# New_Project_2024-11-29_16-29-11.net
KiCad netlist of a schematic drawn in EasyEDA Pro
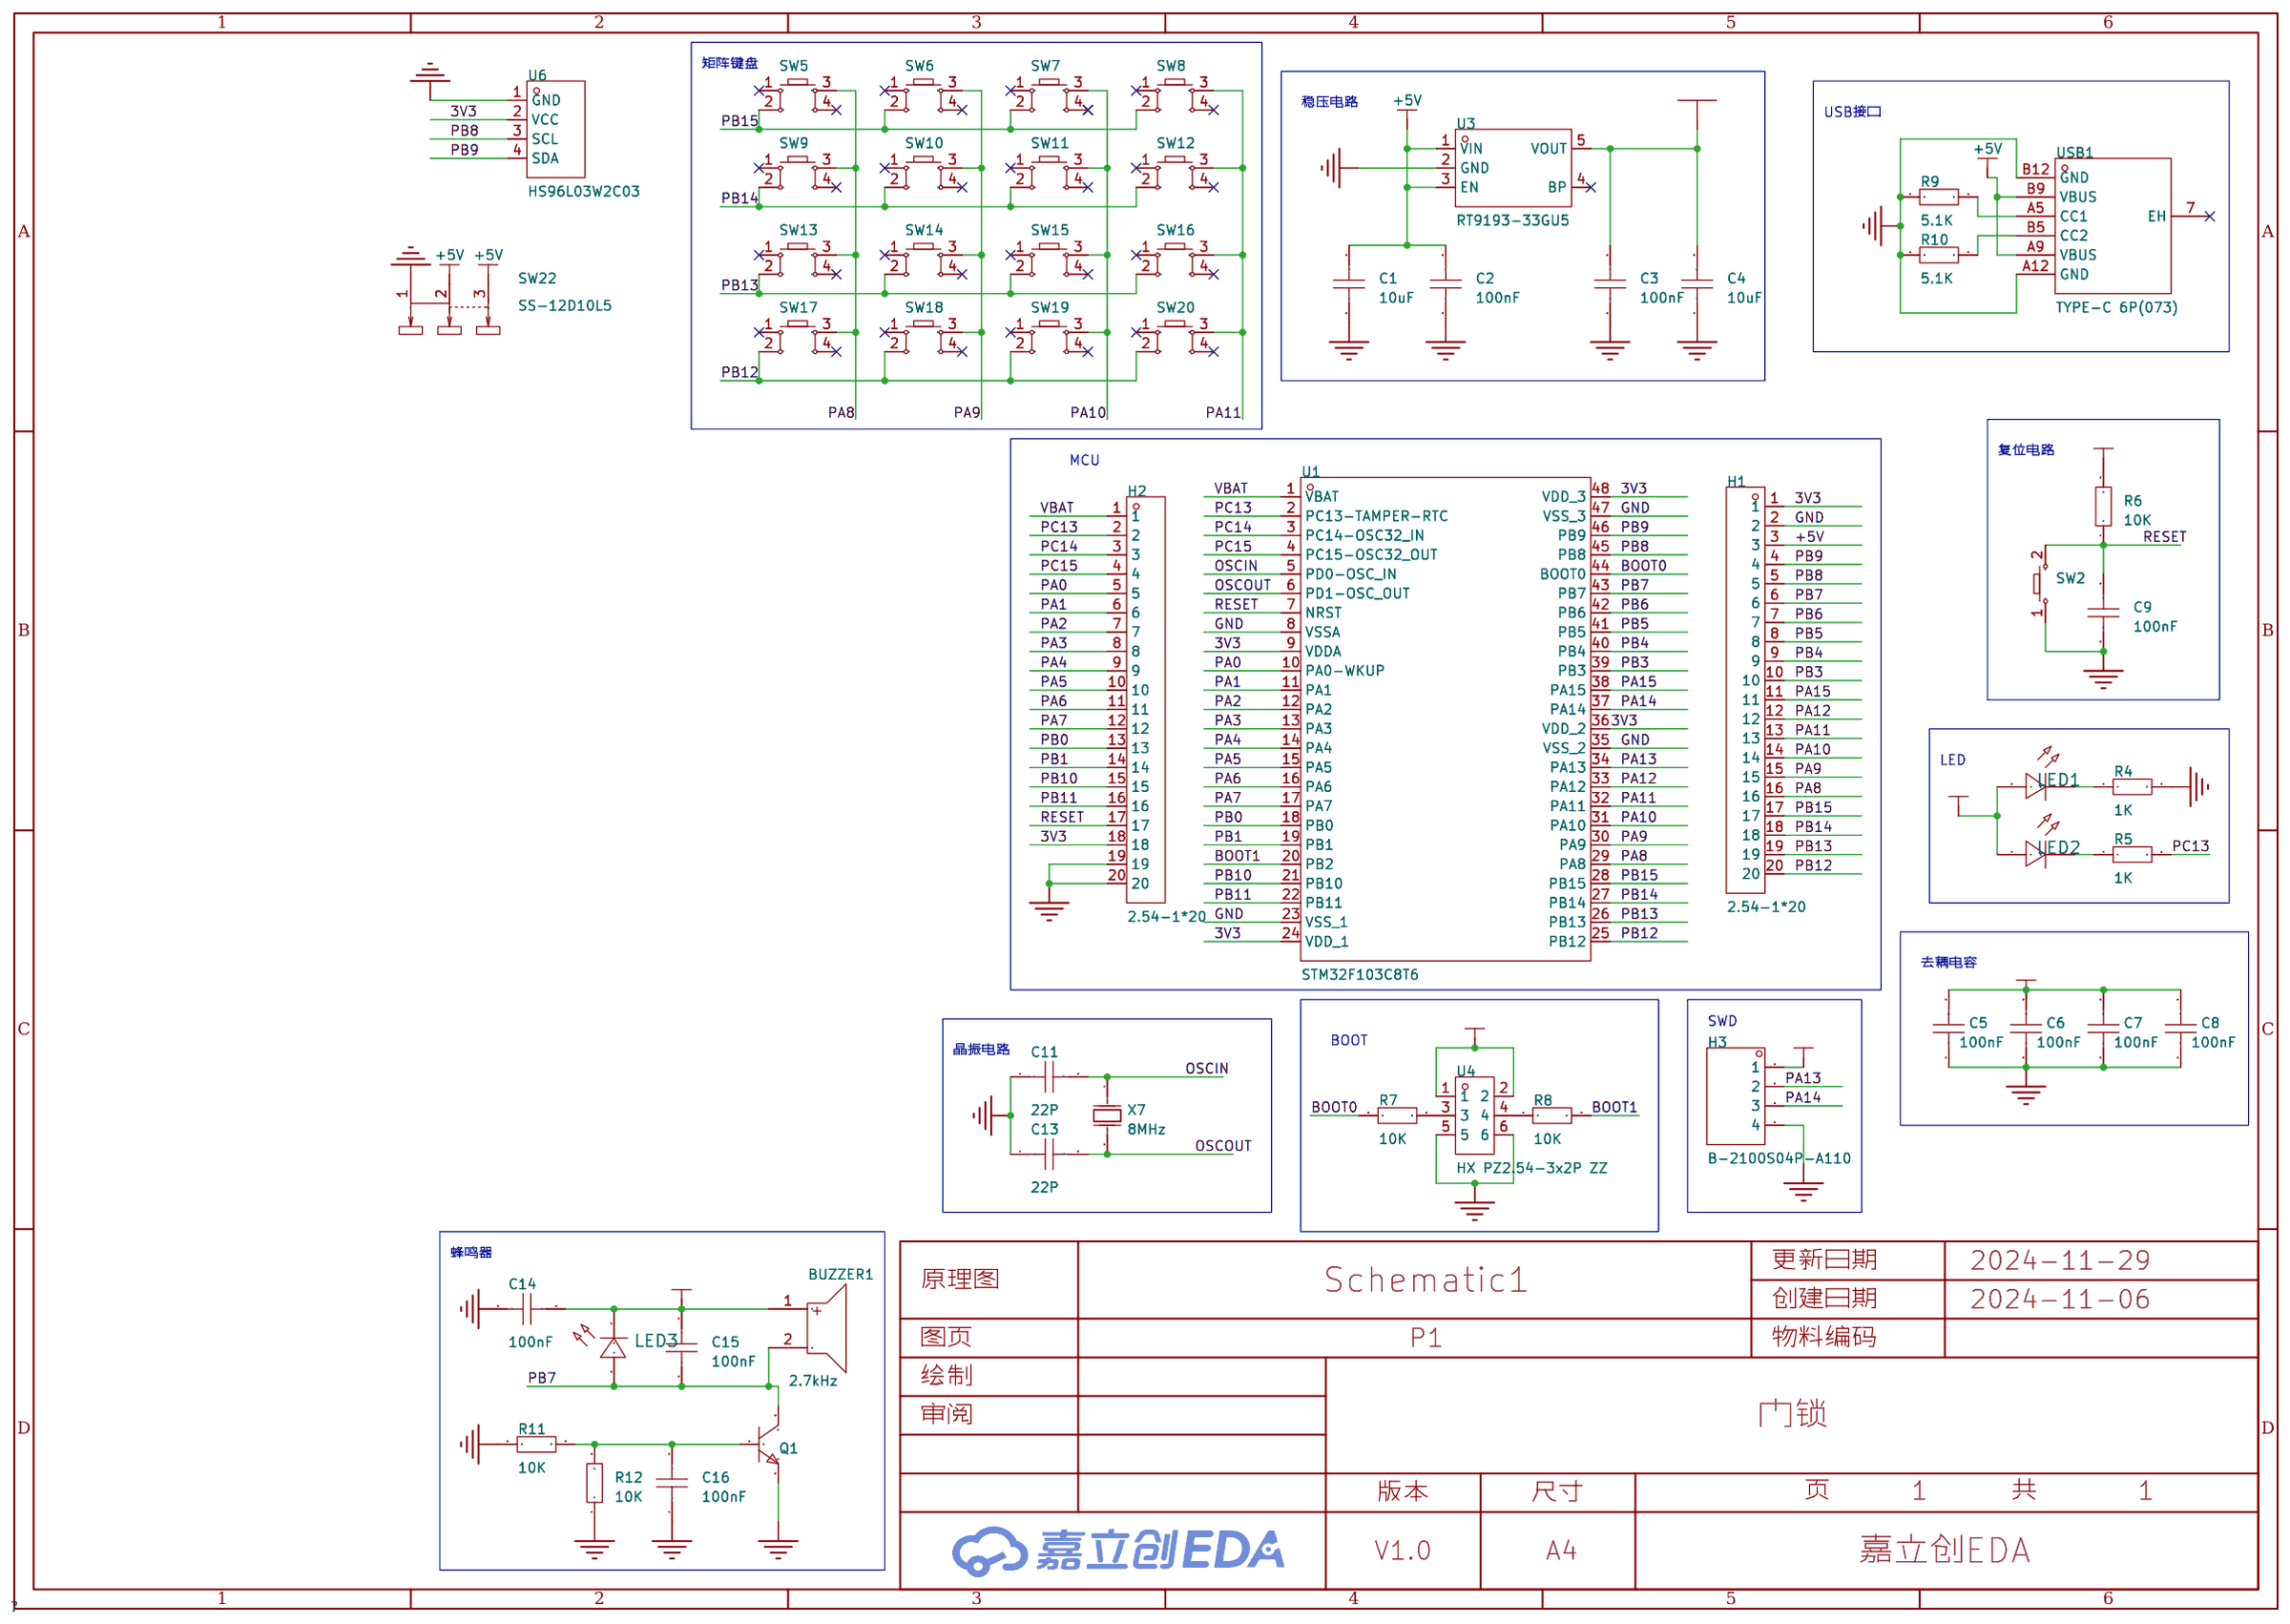
[diagram p0: schematic sheet]

(export (version "E")
  (design (tool "Eeschema 10.0.6"))
  (components
    (comp (ref "BUZZER1")
      (value "2.7kHz")
      (footprint "easyedapro:BUZ-TH_BD9.0-P4.00-D0.6-FD")
      (description "驱动方式:无源(外部驱动);构造类型:电磁式;频率:2.7kHz;声压(SPL):85dB@3V,10cm;")
      (fields (field (name "Manufacturer Part") "QMB-09B-03") (field (name "Manufacturer") "华能"))
      (libsource (lib "easyedapro") (part "QMB-09B-03"))
    )
    (comp (ref "C1")
      (value "10uF")
      (footprint "easyedapro:C0805")
      (libsource (lib "easyedapro") (part "CapAcitance"))
    )
    (comp (ref "C2")
      (value "100nF")
      (footprint "easyedapro:C0805")
      (libsource (lib "easyedapro") (part "CapAcitance"))
    )
    (comp (ref "C3")
      (value "100nF")
      (footprint "easyedapro:C0805")
      (libsource (lib "easyedapro") (part "CapAcitance"))
    )
    (comp (ref "C4")
      (value "10uF")
      (footprint "easyedapro:C0805")
      (libsource (lib "easyedapro") (part "CapAcitance"))
    )
    (comp (ref "C5")
      (value "100nF")
      (footprint "easyedapro:C0805")
      (libsource (lib "easyedapro") (part "CapAcitance"))
    )
    (comp (ref "C6")
      (value "100nF")
      (footprint "easyedapro:C0805")
      (libsource (lib "easyedapro") (part "CapAcitance"))
    )
    (comp (ref "C7")
      (value "100nF")
      (footprint "easyedapro:C0805")
      (libsource (lib "easyedapro") (part "CapAcitance"))
    )
    (comp (ref "C8")
      (value "100nF")
      (footprint "easyedapro:C0805")
      (libsource (lib "easyedapro") (part "CapAcitance"))
    )
    (comp (ref "C9")
      (value "100nF")
      (footprint "easyedapro:C0805")
      (libsource (lib "easyedapro") (part "CapAcitance"))
    )
    (comp (ref "C11")
      (value "22P")
      (footprint "easyedapro:C0805")
      (libsource (lib "easyedapro") (part "CapAcitance"))
    )
    (comp (ref "C13")
      (value "22P")
      (footprint "easyedapro:C0805")
      (libsource (lib "easyedapro") (part "CapAcitance"))
    )
    (comp (ref "C14")
      (value "100nF")
      (footprint "easyedapro:C0805")
      (libsource (lib "easyedapro") (part "CapAcitance"))
    )
    (comp (ref "C15")
      (value "100nF")
      (footprint "easyedapro:C0805")
      (libsource (lib "easyedapro") (part "CapAcitance"))
    )
    (comp (ref "C16")
      (value "100nF")
      (footprint "easyedapro:C0805")
      (libsource (lib "easyedapro") (part "CapAcitance"))
    )
    (comp (ref "H1")
      (value "2.54-1*20")
      (footprint "easyedapro:HDR-TH_20P-P2.54-V-M")
      (description "插针结构:1x20P;间距:2.54mm;排数:单排;总PIN位数:20P;")
      (fields (field (name "Manufacturer") "ZHOURI(洲日)"))
      (libsource (lib "easyedapro") (part "2.54-1*20"))
    )
    (comp (ref "H2")
      (value "2.54-1*20")
      (footprint "easyedapro:HDR-TH_20P-P2.54-V-M")
      (description "插针结构:1x20P;间距:2.54mm;排数:单排;总PIN位数:20P;")
      (fields (field (name "Manufacturer") "ZHOURI(洲日)"))
      (libsource (lib "easyedapro") (part "2.54-1*20"))
    )
    (comp (ref "H3")
      (value "B-2100S04P-A110")
      (footprint "easyedapro:HDR-TH_4P-P2.54-V-M")
      (fields (field (name "Manufacturer") "Ckmtw(灿科盟)"))
      (libsource (lib "easyedapro") (part "Header-Male-2.54_1x4"))
    )
    (comp (ref "LED1")
      (value "~")
      (footprint "easyedapro:LED_0603")
      (libsource (lib "easyedapro") (part "LED_R"))
    )
    (comp (ref "LED2")
      (value "~")
      (footprint "easyedapro:LED_0603")
      (libsource (lib "easyedapro") (part "LED_R"))
    )
    (comp (ref "LED3")
      (value "~")
      (footprint "easyedapro:LED_0603")
      (libsource (lib "easyedapro") (part "LED_R"))
    )
    (comp (ref "Q1")
      (value "~")
      (footprint "easyedapro:S8050_SOT-23")
      (libsource (lib "easyedapro") (part "NPN"))
    )
    (comp (ref "R4") (value "1K") (footprint "easyedapro:R0603") (libsource (lib "easyedapro") (part "电阻")))
    (comp (ref "R5") (value "1K") (footprint "easyedapro:R0603") (libsource (lib "easyedapro") (part "电阻")))
    (comp (ref "R6") (value "10K") (footprint "easyedapro:R0603") (libsource (lib "easyedapro") (part "电阻")))
    (comp (ref "R7") (value "10K") (footprint "easyedapro:R0603") (libsource (lib "easyedapro") (part "电阻")))
    (comp (ref "R8") (value "10K") (footprint "easyedapro:R0603") (libsource (lib "easyedapro") (part "电阻")))
    (comp (ref "R9") (value "5.1K") (footprint "easyedapro:R0603") (libsource (lib "easyedapro") (part "电阻")))
    (comp (ref "R10")
      (value "5.1K")
      (footprint "easyedapro:R0603")
      (libsource (lib "easyedapro") (part "电阻"))
    )
    (comp (ref "R11") (value "10K") (footprint "easyedapro:R0603") (libsource (lib "easyedapro") (part "电阻")))
    (comp (ref "R12") (value "10K") (footprint "easyedapro:R0603") (libsource (lib "easyedapro") (part "电阻")))
    (comp (ref "SW2")
      (value "~")
      (footprint "easyedapro:Key_SMD_3.6x6.1x2.5")
      (libsource (lib "easyedapro") (part "轻触按键x2"))
    )
    (comp (ref "SW5")
      (value "~")
      (footprint "easyedapro:SW-SMD_4P-L6.0-W6.0-P4.50-LS9.0-2")
      (libsource (lib "easyedapro") (part "轻触按键"))
    )
    (comp (ref "SW6")
      (value "~")
      (footprint "easyedapro:SW-SMD_4P-L6.0-W6.0-P4.50-LS9.0-2")
      (libsource (lib "easyedapro") (part "轻触按键"))
    )
    (comp (ref "SW7")
      (value "~")
      (footprint "easyedapro:SW-SMD_4P-L6.0-W6.0-P4.50-LS9.0-2")
      (libsource (lib "easyedapro") (part "轻触按键"))
    )
    (comp (ref "SW8")
      (value "~")
      (footprint "easyedapro:SW-SMD_4P-L6.0-W6.0-P4.50-LS9.0-2")
      (libsource (lib "easyedapro") (part "轻触按键"))
    )
    (comp (ref "SW9")
      (value "~")
      (footprint "easyedapro:SW-SMD_4P-L6.0-W6.0-P4.50-LS9.0-2")
      (libsource (lib "easyedapro") (part "轻触按键"))
    )
    (comp (ref "SW10")
      (value "~")
      (footprint "easyedapro:SW-SMD_4P-L6.0-W6.0-P4.50-LS9.0-2")
      (libsource (lib "easyedapro") (part "轻触按键"))
    )
    (comp (ref "SW11")
      (value "~")
      (footprint "easyedapro:SW-SMD_4P-L6.0-W6.0-P4.50-LS9.0-2")
      (libsource (lib "easyedapro") (part "轻触按键"))
    )
    (comp (ref "SW12")
      (value "~")
      (footprint "easyedapro:SW-SMD_4P-L6.0-W6.0-P4.50-LS9.0-2")
      (libsource (lib "easyedapro") (part "轻触按键"))
    )
    (comp (ref "SW13")
      (value "~")
      (footprint "easyedapro:SW-SMD_4P-L6.0-W6.0-P4.50-LS9.0-2")
      (libsource (lib "easyedapro") (part "轻触按键"))
    )
    (comp (ref "SW14")
      (value "~")
      (footprint "easyedapro:SW-SMD_4P-L6.0-W6.0-P4.50-LS9.0-2")
      (libsource (lib "easyedapro") (part "轻触按键"))
    )
    (comp (ref "SW15")
      (value "~")
      (footprint "easyedapro:SW-SMD_4P-L6.0-W6.0-P4.50-LS9.0-2")
      (libsource (lib "easyedapro") (part "轻触按键"))
    )
    (comp (ref "SW16")
      (value "~")
      (footprint "easyedapro:SW-SMD_4P-L6.0-W6.0-P4.50-LS9.0-2")
      (libsource (lib "easyedapro") (part "轻触按键"))
    )
    (comp (ref "SW17")
      (value "~")
      (footprint "easyedapro:SW-SMD_4P-L6.0-W6.0-P4.50-LS9.0-2")
      (libsource (lib "easyedapro") (part "轻触按键"))
    )
    (comp (ref "SW18")
      (value "~")
      (footprint "easyedapro:SW-SMD_4P-L6.0-W6.0-P4.50-LS9.0-2")
      (libsource (lib "easyedapro") (part "轻触按键"))
    )
    (comp (ref "SW19")
      (value "~")
      (footprint "easyedapro:SW-SMD_4P-L6.0-W6.0-P4.50-LS9.0-2")
      (libsource (lib "easyedapro") (part "轻触按键"))
    )
    (comp (ref "SW20")
      (value "~")
      (footprint "easyedapro:SW-SMD_4P-L6.0-W6.0-P4.50-LS9.0-2")
      (libsource (lib "easyedapro") (part "轻触按键"))
    )
    (comp (ref "SW22")
      (value "SS-12D10L5")
      (footprint "easyedapro:SW-TH_SS-12D10L5")
      (description "电路结构:单刀双掷;安装方式:直插;开关颜色:黑色;额定电流(DC):3A;额定电压(DC):125V;额定电流(AC):3A;额定电压(AC):125V;机械寿命:1万次;")
      (fields (field (name "Manufacturer") "XKB Connectivity(中国星坤)"))
      (libsource (lib "easyedapro") (part "SS-12D10L5"))
    )
    (comp (ref "U1")
      (value "STM32F103C8T6")
      (footprint "easyedapro:LQFP-48_L7.0-W7.0-P0.50-LS9.0-BL")
      (description "CPU内核:ARM-M3;程序存储容量:64KB;RAM总容量:20KB;GPIO端口数量:37;工作电压范围:2V~3.6V;CPU最大主频:72MHz;程序存储器类型:FLASH;")
      (fields (field (name "Manufacturer") "ST(意法半导体)"))
      (libsource (lib "easyedapro") (part "stm32f103c8t6"))
    )
    (comp (ref "U3")
      (value "RT9193-33GU5")
      (footprint "easyedapro:SC-70-5")
      (description "输出类型:固定;最大输入电压:5.5V;输出电压:3.3V;输出电流:300mA;电源纹波抑制比(PSRR):70dB@(100Hz);输出极性:正极;")
      (fields (field (name "Manufacturer") "RICHTEK(立锜)"))
      (libsource (lib "easyedapro") (part "rt9193-33gu5"))
    )
    (comp (ref "U4")
      (value "HX PZ2.54-3x2P ZZ")
      (footprint "easyedapro:hdr-th_6p-p2.54-v-m-r3-c2-s2.54_2")
      (fields (field (name "Manufacturer") "hanxia(韩下)"))
      (libsource (lib "easyedapro") (part "hx pz2.54-3x2p zz"))
    )
    (comp (ref "U6")
      (value "HS96L03W2C03")
      (footprint "easyedapro:OLED-TH_L27.8-W27.2-P2.54_C9900033791")
      (description "主控芯片:SSD1315;接口类型:I2C;尺寸(inch):0.96;像素分辨率:128x64;")
      (fields (field (name "Manufacturer") "HS(汉昇)"))
      (libsource (lib "easyedapro") (part "HS96L03W2C03"))
    )
    (comp (ref "USB1")
      (value "TYPE-C 6P(073)")
      (footprint "easyedapro:TYPE-C-SMD_TYPE-C-6P_5")
      (description "连接器类型:Type-C;标准:USB 3.1;公母:母;安装方式:卧贴;触点数量:6P;端口数量:1;额定电流 - 电源:3A;工作温度范围:-25°C~+85°C;")
      (fields (field (name "Manufacturer") "SHOU HAN(首韩)"))
      (libsource (lib "easyedapro") (part "TYPE-C 6P(073)"))
    )
    (comp (ref "X7")
      (value "8MHz")
      (footprint "easyedapro:OSC-TH_L10.0-W4.5-P5.00")
      (description "晶振类型:直插晶振;频率:8MHz;常温频差:±20ppm;外接负载电容:20pF;频率稳定度(全温):±30ppm;")
      (fields (field (name "Manufacturer Part") "X49SD8MSD2SC") (field (name "Manufacturer") "YXC(扬兴晶振)"))
      (libsource (lib "easyedapro") (part "x49sd8msd2sc"))
    )
  )
  (nets
    (net (code "1") (name "+5V") (class "Default")
      (node (ref "C1") (pin "2") (pinfunction "2_2") (pintype "input"))
      (node (ref "C2") (pin "2") (pinfunction "2_2") (pintype "input"))
      (node (ref "H1") (pin "3") (pinfunction "3_3") (pintype "unspecified"))
      (node (ref "SW22") (pin "2") (pinfunction "2_2") (pintype "unspecified"))
      (node (ref "SW22") (pin "3") (pinfunction "3_3") (pintype "unspecified"))
      (node (ref "U3") (pin "1") (pinfunction "VIN_1") (pintype "unspecified"))
      (node (ref "U3") (pin "3") (pinfunction "EN_3") (pintype "unspecified"))
      (node (ref "USB1") (pin "A9") (pinfunction "VBUS_A9") (pintype "unspecified"))
      (node (ref "USB1") (pin "B9") (pinfunction "VBUS_B9") (pintype "unspecified"))
    )
    (net (code "2") (name "/BOOT0") (class "Default")
      (node (ref "R7") (pin "1") (pinfunction "1_1") (pintype "input"))
      (node (ref "U1") (pin "44") (pinfunction "BOOT0_44") (pintype "unspecified"))
    )
    (net (code "3") (name "/BOOT1") (class "Default")
      (node (ref "R8") (pin "2") (pinfunction "2_2") (pintype "input"))
      (node (ref "U1") (pin "20") (pinfunction "PB2_20") (pintype "unspecified"))
    )
    (net (code "4") (name "/OSCIN") (class "Default")
      (node (ref "C11") (pin "2") (pinfunction "2_2") (pintype "input"))
      (node (ref "U1") (pin "5") (pinfunction "PD0-OSC_IN_5") (pintype "unspecified"))
      (node (ref "X7") (pin "1") (pinfunction "OSC1_1") (pintype "input"))
    )
    (net (code "5") (name "/OSCOUT") (class "Default")
      (node (ref "C13") (pin "2") (pinfunction "2_2") (pintype "input"))
      (node (ref "U1") (pin "6") (pinfunction "PD1-OSC_OUT_6") (pintype "unspecified"))
      (node (ref "X7") (pin "2") (pinfunction "OSC2_2") (pintype "input"))
    )
    (net (code "6") (name "/PA0") (class "Default")
      (node (ref "H2") (pin "5") (pinfunction "5_5") (pintype "unspecified"))
      (node (ref "U1") (pin "10") (pinfunction "PA0-WKUP_10") (pintype "unspecified"))
    )
    (net (code "7") (name "/PA1") (class "Default")
      (node (ref "H2") (pin "6") (pinfunction "6_6") (pintype "unspecified"))
      (node (ref "U1") (pin "11") (pinfunction "PA1_11") (pintype "unspecified"))
    )
    (net (code "8") (name "/PA2") (class "Default")
      (node (ref "H2") (pin "7") (pinfunction "7_7") (pintype "unspecified"))
      (node (ref "U1") (pin "12") (pinfunction "PA2_12") (pintype "unspecified"))
    )
    (net (code "9") (name "/PA3") (class "Default")
      (node (ref "H2") (pin "8") (pinfunction "8_8") (pintype "unspecified"))
      (node (ref "U1") (pin "13") (pinfunction "PA3_13") (pintype "unspecified"))
    )
    (net (code "10") (name "/PA4") (class "Default")
      (node (ref "H2") (pin "9") (pinfunction "9_9") (pintype "unspecified"))
      (node (ref "U1") (pin "14") (pinfunction "PA4_14") (pintype "unspecified"))
    )
    (net (code "11") (name "/PA5") (class "Default")
      (node (ref "H2") (pin "10") (pinfunction "10_10") (pintype "unspecified"))
      (node (ref "U1") (pin "15") (pinfunction "PA5_15") (pintype "unspecified"))
    )
    (net (code "12") (name "/PA6") (class "Default")
      (node (ref "H2") (pin "11") (pinfunction "11_11") (pintype "unspecified"))
      (node (ref "U1") (pin "16") (pinfunction "PA6_16") (pintype "unspecified"))
    )
    (net (code "13") (name "/PA7") (class "Default")
      (node (ref "H2") (pin "12") (pinfunction "12_12") (pintype "unspecified"))
      (node (ref "U1") (pin "17") (pinfunction "PA7_17") (pintype "unspecified"))
    )
    (net (code "14") (name "/PA8") (class "Default")
      (node (ref "H1") (pin "16") (pinfunction "16_16") (pintype "unspecified"))
      (node (ref "SW13") (pin "3") (pinfunction "3_3") (pintype "input"))
      (node (ref "SW17") (pin "3") (pinfunction "3_3") (pintype "input"))
      (node (ref "SW5") (pin "3") (pinfunction "3_3") (pintype "input"))
      (node (ref "SW9") (pin "3") (pinfunction "3_3") (pintype "input"))
      (node (ref "U1") (pin "29") (pinfunction "PA8_29") (pintype "unspecified"))
    )
    (net (code "15") (name "/PA9") (class "Default")
      (node (ref "H1") (pin "15") (pinfunction "15_15") (pintype "unspecified"))
      (node (ref "SW10") (pin "3") (pinfunction "3_3") (pintype "input"))
      (node (ref "SW14") (pin "3") (pinfunction "3_3") (pintype "input"))
      (node (ref "SW18") (pin "3") (pinfunction "3_3") (pintype "input"))
      (node (ref "SW6") (pin "3") (pinfunction "3_3") (pintype "input"))
      (node (ref "U1") (pin "30") (pinfunction "PA9_30") (pintype "unspecified"))
    )
    (net (code "16") (name "/PA10") (class "Default")
      (node (ref "H1") (pin "14") (pinfunction "14_14") (pintype "unspecified"))
      (node (ref "SW11") (pin "3") (pinfunction "3_3") (pintype "input"))
      (node (ref "SW15") (pin "3") (pinfunction "3_3") (pintype "input"))
      (node (ref "SW19") (pin "3") (pinfunction "3_3") (pintype "input"))
      (node (ref "SW7") (pin "3") (pinfunction "3_3") (pintype "input"))
      (node (ref "U1") (pin "31") (pinfunction "PA10_31") (pintype "unspecified"))
    )
    (net (code "17") (name "/PA11") (class "Default")
      (node (ref "H1") (pin "13") (pinfunction "13_13") (pintype "unspecified"))
      (node (ref "SW12") (pin "3") (pinfunction "3_3") (pintype "input"))
      (node (ref "SW16") (pin "3") (pinfunction "3_3") (pintype "input"))
      (node (ref "SW20") (pin "3") (pinfunction "3_3") (pintype "input"))
      (node (ref "SW8") (pin "3") (pinfunction "3_3") (pintype "input"))
      (node (ref "U1") (pin "32") (pinfunction "PA11_32") (pintype "unspecified"))
    )
    (net (code "18") (name "/PA12") (class "Default")
      (node (ref "H1") (pin "12") (pinfunction "12_12") (pintype "unspecified"))
      (node (ref "U1") (pin "33") (pinfunction "PA12_33") (pintype "unspecified"))
    )
    (net (code "19") (name "/PA13") (class "Default")
      (node (ref "H3") (pin "2") (pinfunction "2_2") (pintype "unspecified"))
      (node (ref "U1") (pin "34") (pinfunction "PA13_34") (pintype "unspecified"))
    )
    (net (code "20") (name "/PA14") (class "Default")
      (node (ref "H3") (pin "3") (pinfunction "3_3") (pintype "unspecified"))
      (node (ref "U1") (pin "37") (pinfunction "PA14_37") (pintype "unspecified"))
    )
    (net (code "21") (name "/PA15") (class "Default")
      (node (ref "H1") (pin "11") (pinfunction "11_11") (pintype "unspecified"))
      (node (ref "U1") (pin "38") (pinfunction "PA15_38") (pintype "unspecified"))
    )
    (net (code "22") (name "/PB0") (class "Default")
      (node (ref "H2") (pin "13") (pinfunction "13_13") (pintype "unspecified"))
      (node (ref "U1") (pin "18") (pinfunction "PB0_18") (pintype "unspecified"))
    )
    (net (code "23") (name "/PB1") (class "Default")
      (node (ref "H2") (pin "14") (pinfunction "14_14") (pintype "unspecified"))
      (node (ref "U1") (pin "19") (pinfunction "PB1_19") (pintype "unspecified"))
    )
    (net (code "24") (name "/PB3") (class "Default")
      (node (ref "H1") (pin "10") (pinfunction "10_10") (pintype "unspecified"))
      (node (ref "U1") (pin "39") (pinfunction "PB3_39") (pintype "unspecified"))
    )
    (net (code "25") (name "/PB4") (class "Default")
      (node (ref "H1") (pin "9") (pinfunction "9_9") (pintype "unspecified"))
      (node (ref "U1") (pin "40") (pinfunction "PB4_40") (pintype "unspecified"))
    )
    (net (code "26") (name "/PB5") (class "Default")
      (node (ref "H1") (pin "8") (pinfunction "8_8") (pintype "unspecified"))
      (node (ref "U1") (pin "41") (pinfunction "PB5_41") (pintype "unspecified"))
    )
    (net (code "27") (name "/PB6") (class "Default")
      (node (ref "H1") (pin "7") (pinfunction "7_7") (pintype "unspecified"))
      (node (ref "U1") (pin "42") (pinfunction "PB6_42") (pintype "unspecified"))
    )
    (net (code "28") (name "/PB7") (class "Default")
      (node (ref "BUZZER1") (pin "2") (pinfunction "2_2") (pintype "unspecified"))
      (node (ref "C15") (pin "1") (pinfunction "1_1") (pintype "input"))
      (node (ref "H1") (pin "6") (pinfunction "6_6") (pintype "unspecified"))
      (node (ref "LED3") (pin "2") (pinfunction "A_2") (pintype "input"))
      (node (ref "Q1") (pin "3") (pinfunction "3_3") (pintype "unspecified"))
      (node (ref "U1") (pin "43") (pinfunction "PB7_43") (pintype "unspecified"))
    )
    (net (code "29") (name "/PB8") (class "Default")
      (node (ref "H1") (pin "5") (pinfunction "5_5") (pintype "unspecified"))
      (node (ref "U1") (pin "45") (pinfunction "PB8_45") (pintype "unspecified"))
      (node (ref "U6") (pin "3") (pinfunction "SCL_3") (pintype "unspecified"))
    )
    (net (code "30") (name "/PB9") (class "Default")
      (node (ref "H1") (pin "4") (pinfunction "4_4") (pintype "unspecified"))
      (node (ref "U1") (pin "46") (pinfunction "PB9_46") (pintype "unspecified"))
      (node (ref "U6") (pin "4") (pinfunction "SDA_4") (pintype "unspecified"))
    )
    (net (code "31") (name "/PB10") (class "Default")
      (node (ref "H2") (pin "15") (pinfunction "15_15") (pintype "unspecified"))
      (node (ref "U1") (pin "21") (pinfunction "PB10_21") (pintype "unspecified"))
    )
    (net (code "32") (name "/PB11") (class "Default")
      (node (ref "H2") (pin "16") (pinfunction "16_16") (pintype "unspecified"))
      (node (ref "U1") (pin "22") (pinfunction "PB11_22") (pintype "unspecified"))
    )
    (net (code "33") (name "/PB12") (class "Default")
      (node (ref "H1") (pin "20") (pinfunction "20_20") (pintype "unspecified"))
      (node (ref "SW17") (pin "2") (pinfunction "2_2") (pintype "input"))
      (node (ref "SW18") (pin "2") (pinfunction "2_2") (pintype "input"))
      (node (ref "SW19") (pin "2") (pinfunction "2_2") (pintype "input"))
      (node (ref "SW20") (pin "2") (pinfunction "2_2") (pintype "input"))
      (node (ref "U1") (pin "25") (pinfunction "PB12_25") (pintype "unspecified"))
    )
    (net (code "34") (name "/PB13") (class "Default")
      (node (ref "H1") (pin "19") (pinfunction "19_19") (pintype "unspecified"))
      (node (ref "SW13") (pin "2") (pinfunction "2_2") (pintype "input"))
      (node (ref "SW14") (pin "2") (pinfunction "2_2") (pintype "input"))
      (node (ref "SW15") (pin "2") (pinfunction "2_2") (pintype "input"))
      (node (ref "SW16") (pin "2") (pinfunction "2_2") (pintype "input"))
      (node (ref "U1") (pin "26") (pinfunction "PB13_26") (pintype "unspecified"))
    )
    (net (code "35") (name "/PB14") (class "Default")
      (node (ref "H1") (pin "18") (pinfunction "18_18") (pintype "unspecified"))
      (node (ref "SW10") (pin "2") (pinfunction "2_2") (pintype "input"))
      (node (ref "SW11") (pin "2") (pinfunction "2_2") (pintype "input"))
      (node (ref "SW12") (pin "2") (pinfunction "2_2") (pintype "input"))
      (node (ref "SW9") (pin "2") (pinfunction "2_2") (pintype "input"))
      (node (ref "U1") (pin "27") (pinfunction "PB14_27") (pintype "unspecified"))
    )
    (net (code "36") (name "/PB15") (class "Default")
      (node (ref "H1") (pin "17") (pinfunction "17_17") (pintype "unspecified"))
      (node (ref "SW5") (pin "2") (pinfunction "2_2") (pintype "input"))
      (node (ref "SW6") (pin "2") (pinfunction "2_2") (pintype "input"))
      (node (ref "SW7") (pin "2") (pinfunction "2_2") (pintype "input"))
      (node (ref "SW8") (pin "2") (pinfunction "2_2") (pintype "input"))
      (node (ref "U1") (pin "28") (pinfunction "PB15_28") (pintype "unspecified"))
    )
    (net (code "37") (name "/PC13") (class "Default")
      (node (ref "H2") (pin "2") (pinfunction "2_2") (pintype "unspecified"))
      (node (ref "R5") (pin "2") (pinfunction "2_2") (pintype "input"))
      (node (ref "U1") (pin "2") (pinfunction "PC13-TAMPER-RTC_2") (pintype "unspecified"))
    )
    (net (code "38") (name "/PC14") (class "Default")
      (node (ref "H2") (pin "3") (pinfunction "3_3") (pintype "unspecified"))
      (node (ref "U1") (pin "3") (pinfunction "PC14-OSC32_IN_3") (pintype "unspecified"))
    )
    (net (code "39") (name "/PC15") (class "Default")
      (node (ref "H2") (pin "4") (pinfunction "4_4") (pintype "unspecified"))
      (node (ref "U1") (pin "4") (pinfunction "PC15-OSC32_OUT_4") (pintype "unspecified"))
    )
    (net (code "40") (name "/RESET") (class "Default")
      (node (ref "C9") (pin "2") (pinfunction "2_2") (pintype "input"))
      (node (ref "H2") (pin "17") (pinfunction "17_17") (pintype "unspecified"))
      (node (ref "R6") (pin "1") (pinfunction "1_1") (pintype "input"))
      (node (ref "SW2") (pin "2") (pinfunction "2_2") (pintype "input"))
      (node (ref "U1") (pin "7") (pinfunction "NRST_7") (pintype "unspecified"))
    )
    (net (code "41") (name "/VBAT") (class "Default")
      (node (ref "H2") (pin "1") (pinfunction "1_1") (pintype "unspecified"))
      (node (ref "U1") (pin "1") (pinfunction "VBAT_1") (pintype "unspecified"))
    )
    (net (code "42") (name "3V3") (class "Default")
      (node (ref "BUZZER1") (pin "1") (pinfunction "1_1") (pintype "unspecified"))
      (node (ref "C14") (pin "2") (pinfunction "2_2") (pintype "input"))
      (node (ref "C15") (pin "2") (pinfunction "2_2") (pintype "input"))
      (node (ref "C3") (pin "2") (pinfunction "2_2") (pintype "input"))
      (node (ref "C4") (pin "2") (pinfunction "2_2") (pintype "input"))
      (node (ref "C5") (pin "2") (pinfunction "2_2") (pintype "input"))
      (node (ref "C6") (pin "2") (pinfunction "2_2") (pintype "input"))
      (node (ref "C7") (pin "2") (pinfunction "2_2") (pintype "input"))
      (node (ref "C8") (pin "2") (pinfunction "2_2") (pintype "input"))
      (node (ref "H1") (pin "1") (pinfunction "1_1") (pintype "unspecified"))
      (node (ref "H2") (pin "18") (pinfunction "18_18") (pintype "unspecified"))
      (node (ref "H3") (pin "1") (pinfunction "1_1") (pintype "unspecified"))
      (node (ref "LED1") (pin "2") (pinfunction "A_2") (pintype "input"))
      (node (ref "LED2") (pin "2") (pinfunction "A_2") (pintype "input"))
      (node (ref "LED3") (pin "1") (pinfunction "C_1") (pintype "input"))
      (node (ref "R6") (pin "2") (pinfunction "2_2") (pintype "input"))
      (node (ref "U1") (pin "24") (pinfunction "VDD_1_24") (pintype "unspecified"))
      (node (ref "U1") (pin "36") (pinfunction "VDD_2_36") (pintype "unspecified"))
      (node (ref "U1") (pin "48") (pinfunction "VDD_3_48") (pintype "unspecified"))
      (node (ref "U1") (pin "9") (pinfunction "VDDA_9") (pintype "unspecified"))
      (node (ref "U3") (pin "5") (pinfunction "VOUT_5") (pintype "unspecified"))
      (node (ref "U4") (pin "1") (pinfunction "1_1") (pintype "unspecified"))
      (node (ref "U4") (pin "2") (pinfunction "2_2") (pintype "unspecified"))
      (node (ref "U6") (pin "2") (pinfunction "VCC_2") (pintype "unspecified"))
    )
    (net (code "43") (name "GND") (class "Default")
      (node (ref "C1") (pin "1") (pinfunction "1_1") (pintype "input"))
      (node (ref "C11") (pin "1") (pinfunction "1_1") (pintype "input"))
      (node (ref "C13") (pin "1") (pinfunction "1_1") (pintype "input"))
      (node (ref "C14") (pin "1") (pinfunction "1_1") (pintype "input"))
      (node (ref "C16") (pin "1") (pinfunction "1_1") (pintype "input"))
      (node (ref "C2") (pin "1") (pinfunction "1_1") (pintype "input"))
      (node (ref "C3") (pin "1") (pinfunction "1_1") (pintype "input"))
      (node (ref "C4") (pin "1") (pinfunction "1_1") (pintype "input"))
      (node (ref "C5") (pin "1") (pinfunction "1_1") (pintype "input"))
      (node (ref "C6") (pin "1") (pinfunction "1_1") (pintype "input"))
      (node (ref "C7") (pin "1") (pinfunction "1_1") (pintype "input"))
      (node (ref "C8") (pin "1") (pinfunction "1_1") (pintype "input"))
      (node (ref "C9") (pin "1") (pinfunction "1_1") (pintype "input"))
      (node (ref "H1") (pin "2") (pinfunction "2_2") (pintype "unspecified"))
      (node (ref "H2") (pin "19") (pinfunction "19_19") (pintype "unspecified"))
      (node (ref "H2") (pin "20") (pinfunction "20_20") (pintype "unspecified"))
      (node (ref "H3") (pin "4") (pinfunction "4_4") (pintype "unspecified"))
      (node (ref "Q1") (pin "2") (pinfunction "2_2") (pintype "unspecified"))
      (node (ref "R10") (pin "2") (pinfunction "2_2") (pintype "input"))
      (node (ref "R11") (pin "1") (pinfunction "1_1") (pintype "input"))
      (node (ref "R12") (pin "1") (pinfunction "1_1") (pintype "input"))
      (node (ref "R4") (pin "2") (pinfunction "2_2") (pintype "input"))
      (node (ref "R9") (pin "1") (pinfunction "1_1") (pintype "input"))
      (node (ref "SW2") (pin "1") (pinfunction "1_1") (pintype "input"))
      (node (ref "SW22") (pin "1") (pinfunction "1_1") (pintype "unspecified"))
      (node (ref "U1") (pin "23") (pinfunction "VSS_1_23") (pintype "unspecified"))
      (node (ref "U1") (pin "35") (pinfunction "VSS_2_35") (pintype "unspecified"))
      (node (ref "U1") (pin "47") (pinfunction "VSS_3_47") (pintype "unspecified"))
      (node (ref "U1") (pin "8") (pinfunction "VSSA_8") (pintype "unspecified"))
      (node (ref "U3") (pin "2") (pinfunction "GND_2") (pintype "unspecified"))
      (node (ref "U4") (pin "5") (pinfunction "5_5") (pintype "unspecified"))
      (node (ref "U4") (pin "6") (pinfunction "6_6") (pintype "unspecified"))
      (node (ref "U6") (pin "1") (pinfunction "GND_1") (pintype "unspecified"))
      (node (ref "USB1") (pin "A12") (pinfunction "GND_A12") (pintype "unspecified"))
      (node (ref "USB1") (pin "B12") (pinfunction "GND_B12") (pintype "unspecified"))
    )
    (net (code "44") (name "Net-(C16-Pad2)") (class "Default")
      (node (ref "C16") (pin "2") (pinfunction "2_2") (pintype "input"))
      (node (ref "Q1") (pin "1") (pinfunction "1_1") (pintype "unspecified"))
      (node (ref "R11") (pin "2") (pinfunction "2_2") (pintype "input"))
      (node (ref "R12") (pin "2") (pinfunction "2_2") (pintype "input"))
    )
    (net (code "45") (name "Net-(LED1-C)") (class "Default")
      (node (ref "LED1") (pin "1") (pinfunction "C_1") (pintype "input"))
      (node (ref "R4") (pin "1") (pinfunction "1_1") (pintype "input"))
    )
    (net (code "46") (name "Net-(LED2-C)") (class "Default")
      (node (ref "LED2") (pin "1") (pinfunction "C_1") (pintype "input"))
      (node (ref "R5") (pin "1") (pinfunction "1_1") (pintype "input"))
    )
    (net (code "47") (name "Net-(R7-Pad2)") (class "Default")
      (node (ref "R7") (pin "2") (pinfunction "2_2") (pintype "input"))
      (node (ref "U4") (pin "3") (pinfunction "3_3") (pintype "unspecified"))
    )
    (net (code "48") (name "Net-(R8-Pad1)") (class "Default")
      (node (ref "R8") (pin "1") (pinfunction "1_1") (pintype "input"))
      (node (ref "U4") (pin "4") (pinfunction "4_4") (pintype "unspecified"))
    )
    (net (code "49") (name "Net-(USB1-CC1)") (class "Default")
      (node (ref "R9") (pin "2") (pinfunction "2_2") (pintype "input"))
      (node (ref "USB1") (pin "A5") (pinfunction "CC1_A5") (pintype "unspecified"))
    )
    (net (code "50") (name "Net-(USB1-CC2)") (class "Default")
      (node (ref "R10") (pin "1") (pinfunction "1_1") (pintype "input"))
      (node (ref "USB1") (pin "B5") (pinfunction "CC2_B5") (pintype "unspecified"))
    )
    (net (code "51") (name "unconnected-(SW5-Pad1)") (class "Default")
      (node (ref "SW5") (pin "1") (pinfunction "1_1") (pintype "input+no_connect"))
    )
    (net (code "52") (name "unconnected-(SW5-Pad4)") (class "Default")
      (node (ref "SW5") (pin "4") (pinfunction "4_4") (pintype "input+no_connect"))
    )
    (net (code "53") (name "unconnected-(SW6-Pad1)") (class "Default")
      (node (ref "SW6") (pin "1") (pinfunction "1_1") (pintype "input+no_connect"))
    )
    (net (code "54") (name "unconnected-(SW6-Pad4)") (class "Default")
      (node (ref "SW6") (pin "4") (pinfunction "4_4") (pintype "input+no_connect"))
    )
    (net (code "55") (name "unconnected-(SW7-Pad1)") (class "Default")
      (node (ref "SW7") (pin "1") (pinfunction "1_1") (pintype "input+no_connect"))
    )
    (net (code "56") (name "unconnected-(SW7-Pad4)") (class "Default")
      (node (ref "SW7") (pin "4") (pinfunction "4_4") (pintype "input+no_connect"))
    )
    (net (code "57") (name "unconnected-(SW8-Pad1)") (class "Default")
      (node (ref "SW8") (pin "1") (pinfunction "1_1") (pintype "input+no_connect"))
    )
    (net (code "58") (name "unconnected-(SW8-Pad4)") (class "Default")
      (node (ref "SW8") (pin "4") (pinfunction "4_4") (pintype "input+no_connect"))
    )
    (net (code "59") (name "unconnected-(SW9-Pad1)") (class "Default")
      (node (ref "SW9") (pin "1") (pinfunction "1_1") (pintype "input+no_connect"))
    )
    (net (code "60") (name "unconnected-(SW9-Pad4)") (class "Default")
      (node (ref "SW9") (pin "4") (pinfunction "4_4") (pintype "input+no_connect"))
    )
    (net (code "61") (name "unconnected-(SW10-Pad1)") (class "Default")
      (node (ref "SW10") (pin "1") (pinfunction "1_1") (pintype "input+no_connect"))
    )
    (net (code "62") (name "unconnected-(SW10-Pad4)") (class "Default")
      (node (ref "SW10") (pin "4") (pinfunction "4_4") (pintype "input+no_connect"))
    )
    (net (code "63") (name "unconnected-(SW11-Pad1)") (class "Default")
      (node (ref "SW11") (pin "1") (pinfunction "1_1") (pintype "input+no_connect"))
    )
    (net (code "64") (name "unconnected-(SW11-Pad4)") (class "Default")
      (node (ref "SW11") (pin "4") (pinfunction "4_4") (pintype "input+no_connect"))
    )
    (net (code "65") (name "unconnected-(SW12-Pad1)") (class "Default")
      (node (ref "SW12") (pin "1") (pinfunction "1_1") (pintype "input+no_connect"))
    )
    (net (code "66") (name "unconnected-(SW12-Pad4)") (class "Default")
      (node (ref "SW12") (pin "4") (pinfunction "4_4") (pintype "input+no_connect"))
    )
    (net (code "67") (name "unconnected-(SW13-Pad1)") (class "Default")
      (node (ref "SW13") (pin "1") (pinfunction "1_1") (pintype "input+no_connect"))
    )
    (net (code "68") (name "unconnected-(SW13-Pad4)") (class "Default")
      (node (ref "SW13") (pin "4") (pinfunction "4_4") (pintype "input+no_connect"))
    )
    (net (code "69") (name "unconnected-(SW14-Pad1)") (class "Default")
      (node (ref "SW14") (pin "1") (pinfunction "1_1") (pintype "input+no_connect"))
    )
    (net (code "70") (name "unconnected-(SW14-Pad4)") (class "Default")
      (node (ref "SW14") (pin "4") (pinfunction "4_4") (pintype "input+no_connect"))
    )
    (net (code "71") (name "unconnected-(SW15-Pad1)") (class "Default")
      (node (ref "SW15") (pin "1") (pinfunction "1_1") (pintype "input+no_connect"))
    )
    (net (code "72") (name "unconnected-(SW15-Pad4)") (class "Default")
      (node (ref "SW15") (pin "4") (pinfunction "4_4") (pintype "input+no_connect"))
    )
    (net (code "73") (name "unconnected-(SW16-Pad1)") (class "Default")
      (node (ref "SW16") (pin "1") (pinfunction "1_1") (pintype "input+no_connect"))
    )
    (net (code "74") (name "unconnected-(SW16-Pad4)") (class "Default")
      (node (ref "SW16") (pin "4") (pinfunction "4_4") (pintype "input+no_connect"))
    )
    (net (code "75") (name "unconnected-(SW17-Pad1)") (class "Default")
      (node (ref "SW17") (pin "1") (pinfunction "1_1") (pintype "input+no_connect"))
    )
    (net (code "76") (name "unconnected-(SW17-Pad4)") (class "Default")
      (node (ref "SW17") (pin "4") (pinfunction "4_4") (pintype "input+no_connect"))
    )
    (net (code "77") (name "unconnected-(SW18-Pad1)") (class "Default")
      (node (ref "SW18") (pin "1") (pinfunction "1_1") (pintype "input+no_connect"))
    )
    (net (code "78") (name "unconnected-(SW18-Pad4)") (class "Default")
      (node (ref "SW18") (pin "4") (pinfunction "4_4") (pintype "input+no_connect"))
    )
    (net (code "79") (name "unconnected-(SW19-Pad1)") (class "Default")
      (node (ref "SW19") (pin "1") (pinfunction "1_1") (pintype "input+no_connect"))
    )
    (net (code "80") (name "unconnected-(SW19-Pad4)") (class "Default")
      (node (ref "SW19") (pin "4") (pinfunction "4_4") (pintype "input+no_connect"))
    )
    (net (code "81") (name "unconnected-(SW20-Pad1)") (class "Default")
      (node (ref "SW20") (pin "1") (pinfunction "1_1") (pintype "input+no_connect"))
    )
    (net (code "82") (name "unconnected-(SW20-Pad4)") (class "Default")
      (node (ref "SW20") (pin "4") (pinfunction "4_4") (pintype "input+no_connect"))
    )
    (net (code "83") (name "unconnected-(U3-BP-Pad4)") (class "Default")
      (node (ref "U3") (pin "4") (pinfunction "BP_4") (pintype "unspecified+no_connect"))
    )
    (net (code "84") (name "unconnected-(USB1-EH-Pad7)") (class "Default")
      (node (ref "USB1") (pin "7") (pinfunction "EH_7") (pintype "unspecified+no_connect"))
    )
  )
)
